# Preliminary_PCB_1_0.net
KiCad netlist of a schematic drawn in EAGLE
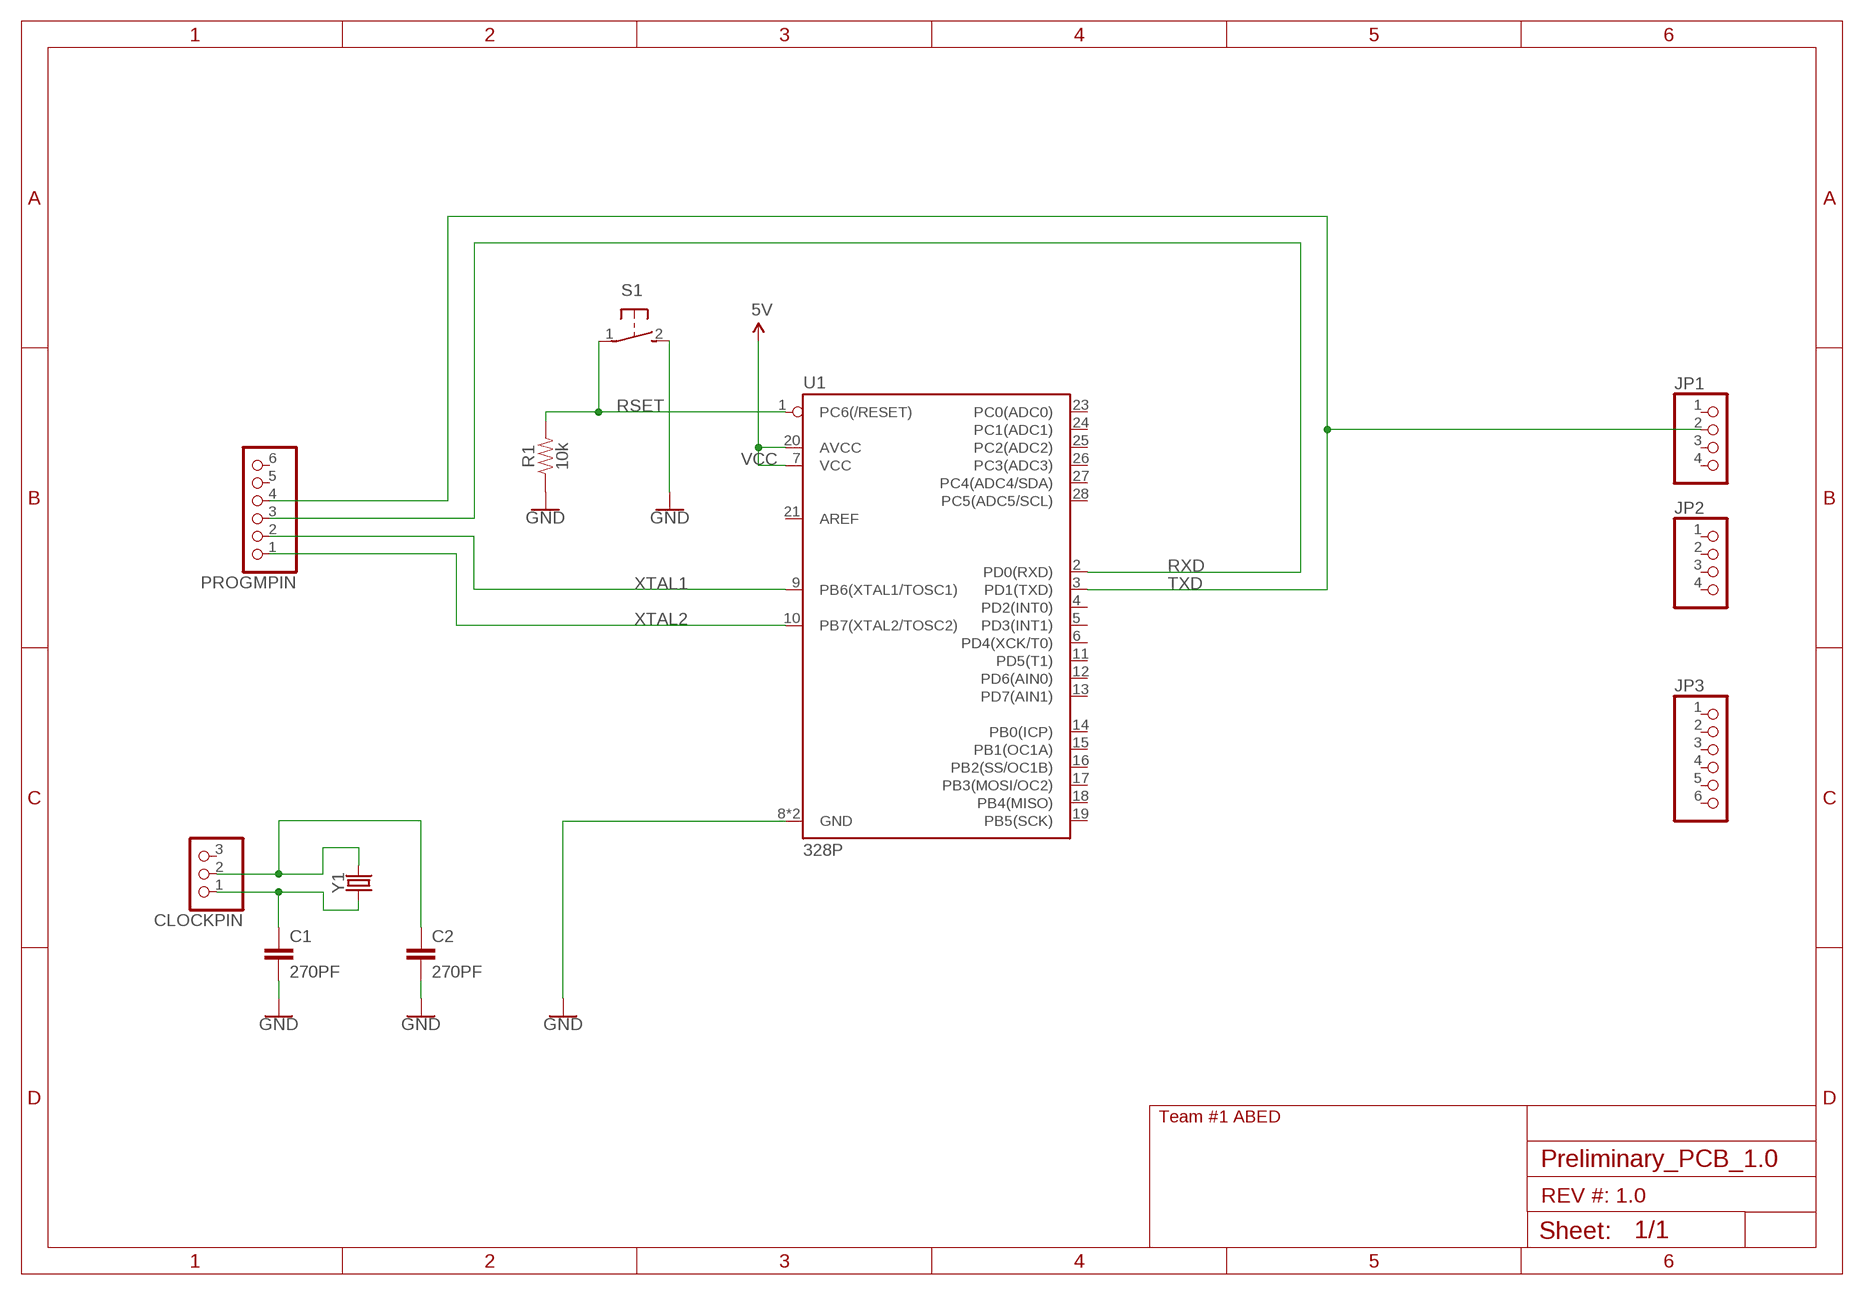
[diagram p0: schematic, sheet 1]

(export (version "E")
  (design (tool "Eeschema 10.0.6"))
  (components
    (comp (ref "C1")
      (value "270PF")
      (footprint "eagle-import:0603")
      (libsource (lib "eagle-import") (part "270PF-0603-50V-5%"))
    )
    (comp (ref "C2")
      (value "270PF")
      (footprint "eagle-import:0603")
      (libsource (lib "eagle-import") (part "270PF-0603-50V-5%"))
    )
    (comp (ref "CLOCKPIN")
      (value "PINHD-1X3CB")
      (footprint "eagle-import:1X03-CLEANBIG")
      (libsource (lib "eagle-import") (part "PINHD-1X3CB"))
    )
    (comp (ref "JP1")
      (value "PINHD-1X4")
      (footprint "eagle-import:1X04")
      (libsource (lib "eagle-import") (part "PINHD-1X4"))
    )
    (comp (ref "JP2")
      (value "PINHD-1X4")
      (footprint "eagle-import:1X04")
      (libsource (lib "eagle-import") (part "PINHD-1X4"))
    )
    (comp (ref "JP3")
      (value "PINHD-1X6")
      (footprint "eagle-import:1X06")
      (libsource (lib "eagle-import") (part "pinhead_325_PINHD-1X6"))
    )
    (comp (ref "PROGMPIN")
      (value "PINHD-1X6")
      (footprint "eagle-import:1X06")
      (libsource (lib "eagle-import") (part "PINHD-1X6"))
    )
    (comp (ref "R1")
      (value "10k")
      (footprint "eagle-import:AXIAL-0.3")
      (libsource (lib "eagle-import") (part "10KOHM-HORIZ-1/4W-1%"))
    )
    (comp (ref "S1")
      (value "31-XX")
      (footprint "eagle-import:B3F-31XX")
      (libsource (lib "eagle-import") (part "31-XX"))
    )
    (comp (ref "U1")
      (value "328P")
      (footprint "eagle-import:DIP28")
      (libsource (lib "eagle-import") (part "ATMEGA328P_PDIP"))
    )
    (comp (ref "Y1")
      (value "CRYSTALPTH-2X6")
      (footprint "eagle-import:CRYSTAL-PTH-2X6-CYL")
      (libsource (lib "eagle-import") (part "CRYSTALPTH-2X6"))
    )
  )
  (nets
    (net (code "1") (name "/RSET") (class "Default")
      (node (ref "R1") (pin "P$2") (pinfunction "2_P$2") (pintype "passive"))
      (node (ref "S1") (pin "1") (pinfunction "P_1") (pintype "passive"))
      (node (ref "U1") (pin "1") (pinfunction "PC6(/RESET)_1") (pintype "bidirectional"))
    )
    (net (code "2") (name "/RXD") (class "Default")
      (node (ref "PROGMPIN") (pin "3") (pinfunction "3_3") (pintype "passive"))
      (node (ref "U1") (pin "2") (pinfunction "PD0(RXD)_2") (pintype "bidirectional"))
    )
    (net (code "3") (name "/TXD") (class "Default")
      (node (ref "JP1") (pin "2") (pinfunction "2_2") (pintype "passive"))
      (node (ref "PROGMPIN") (pin "4") (pinfunction "4_4") (pintype "passive"))
      (node (ref "U1") (pin "3") (pinfunction "PD1(TXD)_3") (pintype "bidirectional"))
    )
    (net (code "4") (name "/XTAL1") (class "Default")
      (node (ref "PROGMPIN") (pin "2") (pinfunction "2_2") (pintype "passive"))
      (node (ref "U1") (pin "9") (pinfunction "PB6(XTAL1/TOSC1)_9") (pintype "bidirectional"))
    )
    (net (code "5") (name "/XTAL2") (class "Default")
      (node (ref "PROGMPIN") (pin "1") (pinfunction "1_1") (pintype "passive"))
      (node (ref "U1") (pin "10") (pinfunction "PB7(XTAL2/TOSC2)_10") (pintype "bidirectional"))
    )
    (net (code "6") (name "5V") (class "Default")
      (node (ref "U1") (pin "20") (pinfunction "AVCC_20") (pintype "bidirectional"))
      (node (ref "U1") (pin "7") (pinfunction "VCC_7") (pintype "bidirectional"))
    )
    (net (code "7") (name "GND") (class "Default")
      (node (ref "C1") (pin "2") (pinfunction "2_2") (pintype "passive"))
      (node (ref "C2") (pin "2") (pinfunction "2_2") (pintype "passive"))
      (node (ref "R1") (pin "P$1") (pinfunction "1_P$1") (pintype "passive"))
      (node (ref "S1") (pin "2") (pinfunction "S_2") (pintype "passive"))
      (node (ref "U1") (pin "22") (pinfunction "GND_22") (pintype "bidirectional"))
      (node (ref "U1") (pin "8") (pinfunction "GND_8") (pintype "bidirectional"))
    )
    (net (code "8") (name "Net-(C1-Pad1)") (class "Default")
      (node (ref "C1") (pin "1") (pinfunction "1_1") (pintype "passive"))
      (node (ref "CLOCKPIN") (pin "1") (pinfunction "1_1") (pintype "passive"))
      (node (ref "Y1") (pin "1") (pinfunction "1_1") (pintype "passive"))
    )
    (net (code "9") (name "Net-(C2-Pad1)") (class "Default")
      (node (ref "C2") (pin "1") (pinfunction "1_1") (pintype "passive"))
      (node (ref "CLOCKPIN") (pin "2") (pinfunction "2_2") (pintype "passive"))
      (node (ref "Y1") (pin "2") (pinfunction "2_2") (pintype "passive"))
    )
    (net (code "10") (name "unconnected-(CLOCKPIN-Pad3)") (class "Default")
      (node (ref "CLOCKPIN") (pin "3") (pinfunction "3_3") (pintype "passive"))
    )
    (net (code "11") (name "unconnected-(JP1-Pad1)") (class "Default")
      (node (ref "JP1") (pin "1") (pinfunction "1_1") (pintype "passive"))
    )
    (net (code "12") (name "unconnected-(JP1-Pad3)") (class "Default")
      (node (ref "JP1") (pin "3") (pinfunction "3_3") (pintype "passive"))
    )
    (net (code "13") (name "unconnected-(JP1-Pad4)") (class "Default")
      (node (ref "JP1") (pin "4") (pinfunction "4_4") (pintype "passive"))
    )
    (net (code "14") (name "unconnected-(JP2-Pad1)") (class "Default")
      (node (ref "JP2") (pin "1") (pinfunction "1_1") (pintype "passive"))
    )
    (net (code "15") (name "unconnected-(JP2-Pad2)") (class "Default")
      (node (ref "JP2") (pin "2") (pinfunction "2_2") (pintype "passive"))
    )
    (net (code "16") (name "unconnected-(JP2-Pad3)") (class "Default")
      (node (ref "JP2") (pin "3") (pinfunction "3_3") (pintype "passive"))
    )
    (net (code "17") (name "unconnected-(JP2-Pad4)") (class "Default")
      (node (ref "JP2") (pin "4") (pinfunction "4_4") (pintype "passive"))
    )
    (net (code "18") (name "unconnected-(JP3-Pad1)") (class "Default")
      (node (ref "JP3") (pin "1") (pinfunction "1_1") (pintype "passive"))
    )
    (net (code "19") (name "unconnected-(JP3-Pad2)") (class "Default")
      (node (ref "JP3") (pin "2") (pinfunction "2_2") (pintype "passive"))
    )
    (net (code "20") (name "unconnected-(JP3-Pad3)") (class "Default")
      (node (ref "JP3") (pin "3") (pinfunction "3_3") (pintype "passive"))
    )
    (net (code "21") (name "unconnected-(JP3-Pad4)") (class "Default")
      (node (ref "JP3") (pin "4") (pinfunction "4_4") (pintype "passive"))
    )
    (net (code "22") (name "unconnected-(JP3-Pad5)") (class "Default")
      (node (ref "JP3") (pin "5") (pinfunction "5_5") (pintype "passive"))
    )
    (net (code "23") (name "unconnected-(JP3-Pad6)") (class "Default")
      (node (ref "JP3") (pin "6") (pinfunction "6_6") (pintype "passive"))
    )
    (net (code "24") (name "unconnected-(PROGMPIN-Pad5)") (class "Default")
      (node (ref "PROGMPIN") (pin "5") (pinfunction "5_5") (pintype "passive"))
    )
    (net (code "25") (name "unconnected-(PROGMPIN-Pad6)") (class "Default")
      (node (ref "PROGMPIN") (pin "6") (pinfunction "6_6") (pintype "passive"))
    )
    (net (code "26") (name "unconnected-(U1-AREF-Pad21)") (class "Default")
      (node (ref "U1") (pin "21") (pinfunction "AREF_21") (pintype "bidirectional"))
    )
    (net (code "27") (name "unconnected-(U1-PB0(ICP)-Pad14)") (class "Default")
      (node (ref "U1") (pin "14") (pinfunction "PB0(ICP)_14") (pintype "bidirectional"))
    )
    (net (code "28") (name "unconnected-(U1-PB1(OC1A)-Pad15)") (class "Default")
      (node (ref "U1") (pin "15") (pinfunction "PB1(OC1A)_15") (pintype "bidirectional"))
    )
    (net (code "29") (name "unconnected-(U1-PB2(SS{slash}OC1B)-Pad16)") (class "Default")
      (node (ref "U1") (pin "16") (pinfunction "PB2(SS/OC1B)_16") (pintype "bidirectional"))
    )
    (net (code "30") (name "unconnected-(U1-PB3(MOSI{slash}OC2)-Pad17)") (class "Default")
      (node (ref "U1") (pin "17") (pinfunction "PB3(MOSI/OC2)_17") (pintype "bidirectional"))
    )
    (net (code "31") (name "unconnected-(U1-PB4(MISO)-Pad18)") (class "Default")
      (node (ref "U1") (pin "18") (pinfunction "PB4(MISO)_18") (pintype "bidirectional"))
    )
    (net (code "32") (name "unconnected-(U1-PB5(SCK)-Pad19)") (class "Default")
      (node (ref "U1") (pin "19") (pinfunction "PB5(SCK)_19") (pintype "bidirectional"))
    )
    (net (code "33") (name "unconnected-(U1-PC0(ADC0)-Pad23)") (class "Default")
      (node (ref "U1") (pin "23") (pinfunction "PC0(ADC0)_23") (pintype "bidirectional"))
    )
    (net (code "34") (name "unconnected-(U1-PC1(ADC1)-Pad24)") (class "Default")
      (node (ref "U1") (pin "24") (pinfunction "PC1(ADC1)_24") (pintype "bidirectional"))
    )
    (net (code "35") (name "unconnected-(U1-PC2(ADC2)-Pad25)") (class "Default")
      (node (ref "U1") (pin "25") (pinfunction "PC2(ADC2)_25") (pintype "bidirectional"))
    )
    (net (code "36") (name "unconnected-(U1-PC3(ADC3)-Pad26)") (class "Default")
      (node (ref "U1") (pin "26") (pinfunction "PC3(ADC3)_26") (pintype "bidirectional"))
    )
    (net (code "37") (name "unconnected-(U1-PC4(ADC4{slash}SDA)-Pad27)") (class "Default")
      (node (ref "U1") (pin "27") (pinfunction "PC4(ADC4/SDA)_27") (pintype "bidirectional"))
    )
    (net (code "38") (name "unconnected-(U1-PC5(ADC5{slash}SCL)-Pad28)") (class "Default")
      (node (ref "U1") (pin "28") (pinfunction "PC5(ADC5/SCL)_28") (pintype "bidirectional"))
    )
    (net (code "39") (name "unconnected-(U1-PD2(INT0)-Pad4)") (class "Default")
      (node (ref "U1") (pin "4") (pinfunction "PD2(INT0)_4") (pintype "bidirectional"))
    )
    (net (code "40") (name "unconnected-(U1-PD3(INT1)-Pad5)") (class "Default")
      (node (ref "U1") (pin "5") (pinfunction "PD3(INT1)_5") (pintype "bidirectional"))
    )
    (net (code "41") (name "unconnected-(U1-PD4(XCK{slash}T0)-Pad6)") (class "Default")
      (node (ref "U1") (pin "6") (pinfunction "PD4(XCK/T0)_6") (pintype "bidirectional"))
    )
    (net (code "42") (name "unconnected-(U1-PD5(T1)-Pad11)") (class "Default")
      (node (ref "U1") (pin "11") (pinfunction "PD5(T1)_11") (pintype "bidirectional"))
    )
    (net (code "43") (name "unconnected-(U1-PD6(AIN0)-Pad12)") (class "Default")
      (node (ref "U1") (pin "12") (pinfunction "PD6(AIN0)_12") (pintype "bidirectional"))
    )
    (net (code "44") (name "unconnected-(U1-PD7(AIN1)-Pad13)") (class "Default")
      (node (ref "U1") (pin "13") (pinfunction "PD7(AIN1)_13") (pintype "bidirectional"))
    )
  )
)
